# EE318.net
KiCad netlist of a schematic drawn in Altium Designer
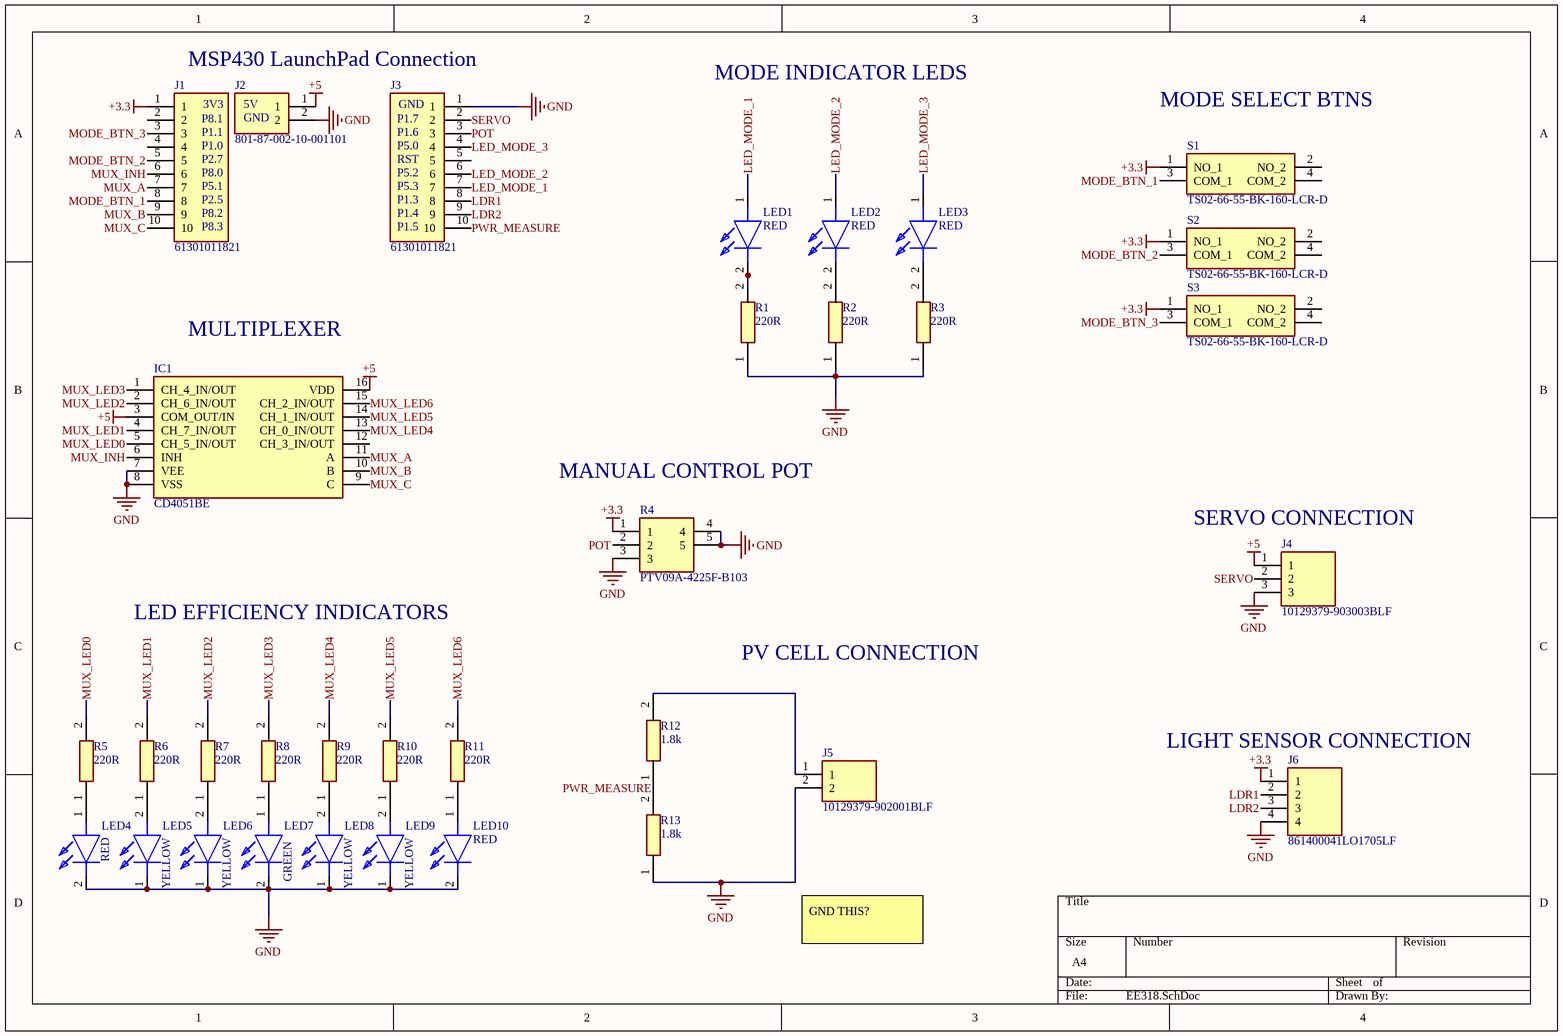
[diagram p0: EE318.SchDoc]

(export (version "E")
  (design (tool "Eeschema 10.0.6"))
  (components
    (comp (ref "IC1")
      (value "CD4051BE")
      (footprint "EE318-PcbLib:DIP794W53P254L1930H508Q16N")
      (description "Multiplexer")
      (fields (field (name "MOUSER PART NUMBER") "595-CD4051BE"))
      (libsource (lib "EE318-Schlib") (part "CD4051BE"))
    )
    (comp (ref "J1")
      (value "61301011821")
      (footprint "EE318-PcbLib:RHDR10W60P0X254_1X10_2590X250X850P")
      (description "Connector")
      (fields (field (name "MOUSER PART NUMBER") "710-61301011821"))
      (libsource (lib "") (part "61301011821_1"))
    )
    (comp (ref "J2")
      (value "801-87-002-10-001101")
      (footprint "EE318-PcbLib:RHDR2W60P0X254_1X2_508X254X700P")
      (description "Connector")
      (fields (field (name "MOUSER PART NUMBER") "437-8018700210001101"))
      (libsource (lib "EE318-Schlib") (part "801-87-002-10-001101"))
    )
    (comp (ref "J3")
      (value "61301011821")
      (footprint "EE318-PcbLib:RHDR10W60P0X254_1X10_2590X250X850P")
      (description "Connector")
      (fields (field (name "MOUSER PART NUMBER") "710-61301011821"))
      (libsource (lib "EE318-Schlib") (part "61301011821"))
    )
    (comp (ref "J4")
      (value "10129379-903003BLF")
      (footprint "EE318-PcbLib:10129379903003BLF")
      (description "Connector")
      (fields (field (name "MOUSER PART NUMBER") "649-1012937990303BLF"))
      (libsource (lib "EE318-Schlib") (part "10129379-903003BLF"))
    )
    (comp (ref "J5")
      (value "10129379-902001BLF")
      (footprint "EE318-PcbLib:HDRRA2W67P0X254_1X2_508X254X241P")
      (description "Connector")
      (fields (field (name "MOUSER PART NUMBER") "649-1012937990201BLF"))
      (libsource (lib "EE318-Schlib") (part "10129379-902001BLF"))
    )
    (comp (ref "J6")
      (value "861400041LO1705LF")
      (footprint "EE318-PcbLib:HDRRA4W63P0X254_1X4_1016X260X264P")
      (description "Connector")
      (fields (field (name "MOUSER PART NUMBER") "649-86140041LO1705LF"))
      (libsource (lib "EE318-Schlib") (part "861400041LO1705LF"))
    )
    (comp (ref "LED1")
      (value "RED")
      (footprint "EE318-PcbLib:C503BRCNCW0Z0AA2")
      (description "LED")
      (fields
        (field (name "MANUFACTURER_PART_NUMBER") "C503B-RCN-CW0Z0AA2")
        (field (name "MOUSER PART NUMBER") "941-C503BRCNCW0Z0AA2")
      )
      (libsource (lib "EE318-Schlib") (part "C503B-RCN-CW0Z0AA2"))
    )
    (comp (ref "LED2")
      (value "RED")
      (footprint "EE318-PcbLib:C503BRCNCW0Z0AA2")
      (description "LED")
      (fields
        (field (name "MANUFACTURER_PART_NUMBER") "C503B-RCN-CW0Z0AA2")
        (field (name "MOUSER PART NUMBER") "941-C503BRCNCW0Z0AA2")
      )
      (libsource (lib "EE318-Schlib") (part "C503B-RCN-CW0Z0AA2"))
    )
    (comp (ref "LED3")
      (value "RED")
      (footprint "EE318-PcbLib:C503BRCNCW0Z0AA2")
      (description "LED")
      (fields
        (field (name "MANUFACTURER_PART_NUMBER") "C503B-RCN-CW0Z0AA2")
        (field (name "MOUSER PART NUMBER") "941-C503BRCNCW0Z0AA2")
      )
      (libsource (lib "EE318-Schlib") (part "C503B-RCN-CW0Z0AA2"))
    )
    (comp (ref "LED4")
      (value "RED")
      (footprint "EE318-PcbLib:C503BRCNCW0Z0AA2")
      (description "LED")
      (fields
        (field (name "MANUFACTURER_PART_NUMBER") "C503B-RCN-CW0Z0AA2")
        (field (name "MOUSER PART NUMBER") "941-C503BRCNCW0Z0AA2")
      )
      (libsource (lib "EE318-Schlib") (part "C503B-RCN-CW0Z0AA2"))
    )
    (comp (ref "LED5")
      (value "YELLOW")
      (footprint "EE318-PcbLib:151051YS04000")
      (description "LED")
      (fields
        (field (name "MANUFACTURER_PART_NUMBER") "151051YS04000")
        (field (name "MOUSER PART NUMBER") "710-151051YS04000")
      )
      (libsource (lib "EE318-Schlib") (part "151051YS04000"))
    )
    (comp (ref "LED6")
      (value "YELLOW")
      (footprint "EE318-PcbLib:151051YS04000")
      (description "LED")
      (fields
        (field (name "MANUFACTURER_PART_NUMBER") "151051YS04000")
        (field (name "MOUSER PART NUMBER") "710-151051YS04000")
      )
      (libsource (lib "EE318-Schlib") (part "151051YS04000"))
    )
    (comp (ref "LED7")
      (value "GREEN")
      (footprint "EE318-PcbLib:C503BGANCB0F0791")
      (description "LED")
      (fields
        (field (name "MANUFACTURER_PART_NUMBER") "C503B-GAN-CB0F0791")
        (field (name "MOUSER PART NUMBER") "941-C503BGANCB0F0791")
      )
      (libsource (lib "EE318-Schlib") (part "C503B-GAN-CB0F0791"))
    )
    (comp (ref "LED8")
      (value "YELLOW")
      (footprint "EE318-PcbLib:151051YS04000")
      (description "LED")
      (fields
        (field (name "MANUFACTURER_PART_NUMBER") "151051YS04000")
        (field (name "MOUSER PART NUMBER") "710-151051YS04000")
      )
      (libsource (lib "EE318-Schlib") (part "151051YS04000"))
    )
    (comp (ref "LED9")
      (value "YELLOW")
      (footprint "EE318-PcbLib:151051YS04000")
      (description "LED")
      (fields
        (field (name "MANUFACTURER_PART_NUMBER") "151051YS04000")
        (field (name "MOUSER PART NUMBER") "710-151051YS04000")
      )
      (libsource (lib "EE318-Schlib") (part "151051YS04000"))
    )
    (comp (ref "LED10")
      (value "RED")
      (footprint "EE318-PcbLib:C503BRCNCW0Z0AA2")
      (description "LED")
      (fields
        (field (name "MANUFACTURER_PART_NUMBER") "C503B-RCN-CW0Z0AA2")
        (field (name "MOUSER PART NUMBER") "941-C503BRCNCW0Z0AA2")
      )
      (libsource (lib "EE318-Schlib") (part "C503B-RCN-CW0Z0AA2"))
    )
    (comp (ref "R1")
      (value "220R")
      (footprint "SamacSys:RESC3116X65N")
      (description "Resistor")
      (fields
        (field (name "MANUFACTURER_PART_NUMBER") "CRS1206QFX-1002ELF")
        (field (name "MOUSER PART NUMBER") "652-CRS1206QFX-1002E")
      )
      (libsource (lib "*") (part "CRS1206QFX-1002ELF"))
    )
    (comp (ref "R2")
      (value "220R")
      (footprint "SamacSys:RESC3116X65N")
      (description "Resistor")
      (fields
        (field (name "MANUFACTURER_PART_NUMBER") "CRS1206QFX-1002ELF")
        (field (name "MOUSER PART NUMBER") "652-CRS1206QFX-1002E")
      )
      (libsource (lib "*") (part "CRS1206QFX-1002ELF"))
    )
    (comp (ref "R3")
      (value "220R")
      (footprint "SamacSys:RESC3116X65N")
      (description "Resistor")
      (fields
        (field (name "MANUFACTURER_PART_NUMBER") "CRS1206QFX-1002ELF")
        (field (name "MOUSER PART NUMBER") "652-CRS1206QFX-1002E")
      )
      (libsource (lib "*") (part "CRS1206QFX-1002ELF"))
    )
    (comp (ref "R4")
      (value "PTV09A-4225F-B103")
      (footprint "EE318-PcbLib:PTV09A4020FB103")
      (description "Potentiometer")
      (fields (field (name "RS PART NUMBER") "8274990P"))
      (libsource (lib "EE318-Schlib") (part "PTV09A-4225F-B103"))
    )
    (comp (ref "R5")
      (value "220R")
      (footprint "SamacSys:RESC3116X65N")
      (description "Resistor")
      (fields
        (field (name "MANUFACTURER_PART_NUMBER") "CRS1206QFX-1002ELF")
        (field (name "MOUSER PART NUMBER") "652-CRS1206QFX-1002E")
      )
      (libsource (lib "*") (part "CRS1206QFX-1002ELF"))
    )
    (comp (ref "R6")
      (value "220R")
      (footprint "SamacSys:RESC3116X65N")
      (description "Resistor")
      (fields
        (field (name "MANUFACTURER_PART_NUMBER") "CRS1206QFX-1002ELF")
        (field (name "MOUSER PART NUMBER") "652-CRS1206QFX-1002E")
      )
      (libsource (lib "*") (part "CRS1206QFX-1002ELF"))
    )
    (comp (ref "R7")
      (value "220R")
      (footprint "SamacSys:RESC3116X65N")
      (description "Resistor")
      (fields
        (field (name "MANUFACTURER_PART_NUMBER") "CRS1206QFX-1002ELF")
        (field (name "MOUSER PART NUMBER") "652-CRS1206QFX-1002E")
      )
      (libsource (lib "*") (part "CRS1206QFX-1002ELF"))
    )
    (comp (ref "R8")
      (value "220R")
      (footprint "SamacSys:RESC3116X65N")
      (description "Resistor")
      (fields
        (field (name "MANUFACTURER_PART_NUMBER") "CRS1206QFX-1002ELF")
        (field (name "MOUSER PART NUMBER") "652-CRS1206QFX-1002E")
      )
      (libsource (lib "*") (part "CRS1206QFX-1002ELF"))
    )
    (comp (ref "R9")
      (value "220R")
      (footprint "SamacSys:RESC3116X65N")
      (description "Resistor")
      (fields
        (field (name "MANUFACTURER_PART_NUMBER") "CRS1206QFX-1002ELF")
        (field (name "MOUSER PART NUMBER") "652-CRS1206QFX-1002E")
      )
      (libsource (lib "*") (part "CRS1206QFX-1002ELF"))
    )
    (comp (ref "R10")
      (value "220R")
      (footprint "SamacSys:RESC3116X65N")
      (description "Resistor")
      (fields
        (field (name "MANUFACTURER_PART_NUMBER") "CRS1206QFX-1002ELF")
        (field (name "MOUSER PART NUMBER") "652-CRS1206QFX-1002E")
      )
      (libsource (lib "*") (part "CRS1206QFX-1002ELF"))
    )
    (comp (ref "R11")
      (value "220R")
      (footprint "SamacSys:RESC3116X65N")
      (description "Resistor")
      (fields
        (field (name "MANUFACTURER_PART_NUMBER") "CRS1206QFX-1002ELF")
        (field (name "MOUSER PART NUMBER") "652-CRS1206QFX-1002E")
      )
      (libsource (lib "*") (part "CRS1206QFX-1002ELF"))
    )
    (comp (ref "R12")
      (value "1.8k")
      (footprint "SamacSys:RESC3116X65N")
      (description "Resistor")
      (fields
        (field (name "MANUFACTURER_PART_NUMBER") "CRS1206QFX-1002ELF")
        (field (name "MOUSER PART NUMBER") "652-CRS1206QFX-1002E")
      )
      (libsource (lib "*") (part "CRS1206QFX-1002ELF"))
    )
    (comp (ref "R13")
      (value "1.8k")
      (footprint "SamacSys:RESC3116X65N")
      (description "Resistor")
      (fields
        (field (name "MANUFACTURER_PART_NUMBER") "CRS1206QFX-1002ELF")
        (field (name "MOUSER PART NUMBER") "652-CRS1206QFX-1002E")
      )
      (libsource (lib "*") (part "CRS1206QFX-1002ELF"))
    )
    (comp (ref "S1")
      (value "TS02-66-55-BK-160-LCR-D")
      (footprint "EE318-PcbLib:TS026655BK160LCRD")
      (description "Switch")
      (fields (field (name "MOUSER PART NUMBER") "179-TS026655BK160LCR"))
      (libsource (lib "EE318-Schlib") (part "TS02-66-55-BK-160-LCR-D"))
    )
    (comp (ref "S2")
      (value "TS02-66-55-BK-160-LCR-D")
      (footprint "EE318-PcbLib:TS026655BK160LCRD")
      (description "Switch")
      (fields (field (name "MOUSER PART NUMBER") "179-TS026655BK160LCR"))
      (libsource (lib "EE318-Schlib") (part "TS02-66-55-BK-160-LCR-D"))
    )
    (comp (ref "S3")
      (value "TS02-66-55-BK-160-LCR-D")
      (footprint "EE318-PcbLib:TS026655BK160LCRD")
      (description "Switch")
      (fields (field (name "MOUSER PART NUMBER") "179-TS026655BK160LCR"))
      (libsource (lib "EE318-Schlib") (part "TS02-66-55-BK-160-LCR-D"))
    )
  )
  (nets
    (net (code "1") (name "+3.3") (class "Default")
      (node (ref "J1") (pin "1") (pinfunction "1_1") (pintype "passive"))
      (node (ref "J6") (pin "1") (pinfunction "1_1") (pintype "passive"))
      (node (ref "R4") (pin "1") (pinfunction "1_1") (pintype "passive"))
      (node (ref "S1") (pin "1") (pinfunction "NO_1_1") (pintype "passive"))
      (node (ref "S2") (pin "1") (pinfunction "NO_1_1") (pintype "passive"))
      (node (ref "S3") (pin "1") (pinfunction "NO_1_1") (pintype "passive"))
    )
    (net (code "2") (name "+5") (class "Default")
      (node (ref "IC1") (pin "16") (pinfunction "VDD_16") (pintype "passive"))
      (node (ref "IC1") (pin "3") (pinfunction "COM_OUT/IN_3") (pintype "passive"))
      (node (ref "J2") (pin "1") (pinfunction "1_1") (pintype "passive"))
      (node (ref "J4") (pin "1") (pinfunction "1_1") (pintype "passive"))
    )
    (net (code "3") (name "/LDR1") (class "Default")
      (node (ref "J3") (pin "8") (pinfunction "8_8") (pintype "passive"))
      (node (ref "J6") (pin "2") (pinfunction "2_2") (pintype "passive"))
    )
    (net (code "4") (name "/LDR2") (class "Default")
      (node (ref "J3") (pin "9") (pinfunction "9_9") (pintype "passive"))
      (node (ref "J6") (pin "3") (pinfunction "3_3") (pintype "passive"))
    )
    (net (code "5") (name "/LED_MODE_1") (class "Default")
      (node (ref "J3") (pin "7") (pinfunction "7_7") (pintype "passive"))
      (node (ref "LED1") (pin "1") (pinfunction "A_1") (pintype "passive"))
    )
    (net (code "6") (name "/LED_MODE_2") (class "Default")
      (node (ref "J3") (pin "6") (pinfunction "6_6") (pintype "passive"))
      (node (ref "LED2") (pin "1") (pinfunction "A_1") (pintype "passive"))
    )
    (net (code "7") (name "/LED_MODE_3") (class "Default")
      (node (ref "J3") (pin "4") (pinfunction "4_4") (pintype "passive"))
      (node (ref "LED3") (pin "1") (pinfunction "A_1") (pintype "passive"))
    )
    (net (code "8") (name "/MODE_BTN_1") (class "Default")
      (node (ref "J1") (pin "8") (pinfunction "8_8") (pintype "passive"))
      (node (ref "S1") (pin "3") (pinfunction "COM_1_3") (pintype "passive"))
    )
    (net (code "9") (name "/MODE_BTN_2") (class "Default")
      (node (ref "J1") (pin "5") (pinfunction "5_5") (pintype "passive"))
      (node (ref "S2") (pin "3") (pinfunction "COM_1_3") (pintype "passive"))
    )
    (net (code "10") (name "/MODE_BTN_3") (class "Default")
      (node (ref "J1") (pin "3") (pinfunction "3_3") (pintype "passive"))
      (node (ref "S3") (pin "3") (pinfunction "COM_1_3") (pintype "passive"))
    )
    (net (code "11") (name "/MUX_A") (class "Default")
      (node (ref "IC1") (pin "11") (pinfunction "A_11") (pintype "passive"))
      (node (ref "J1") (pin "7") (pinfunction "7_7") (pintype "passive"))
    )
    (net (code "12") (name "/MUX_B") (class "Default")
      (node (ref "IC1") (pin "10") (pinfunction "B_10") (pintype "passive"))
      (node (ref "J1") (pin "9") (pinfunction "9_9") (pintype "passive"))
    )
    (net (code "13") (name "/MUX_C") (class "Default")
      (node (ref "IC1") (pin "9") (pinfunction "C_9") (pintype "passive"))
      (node (ref "J1") (pin "10") (pinfunction "10_10") (pintype "passive"))
    )
    (net (code "14") (name "/MUX_INH") (class "Default")
      (node (ref "IC1") (pin "6") (pinfunction "INH_6") (pintype "passive"))
      (node (ref "J1") (pin "6") (pinfunction "6_6") (pintype "passive"))
    )
    (net (code "15") (name "/MUX_LED0") (class "Default")
      (node (ref "IC1") (pin "5") (pinfunction "CH_5_IN/OUT_5") (pintype "passive"))
      (node (ref "R5") (pin "2") (pinfunction "2_2") (pintype "passive"))
    )
    (net (code "16") (name "/MUX_LED1") (class "Default")
      (node (ref "IC1") (pin "4") (pinfunction "CH_7_IN/OUT_4") (pintype "passive"))
      (node (ref "R6") (pin "2") (pinfunction "2_2") (pintype "passive"))
    )
    (net (code "17") (name "/MUX_LED2") (class "Default")
      (node (ref "IC1") (pin "2") (pinfunction "CH_6_IN/OUT_2") (pintype "passive"))
      (node (ref "R7") (pin "2") (pinfunction "2_2") (pintype "passive"))
    )
    (net (code "18") (name "/MUX_LED3") (class "Default")
      (node (ref "IC1") (pin "1") (pinfunction "CH_4_IN/OUT_1") (pintype "passive"))
      (node (ref "R8") (pin "2") (pinfunction "2_2") (pintype "passive"))
    )
    (net (code "19") (name "/MUX_LED4") (class "Default")
      (node (ref "IC1") (pin "13") (pinfunction "CH_0_IN/OUT_13") (pintype "passive"))
      (node (ref "R9") (pin "2") (pinfunction "2_2") (pintype "passive"))
    )
    (net (code "20") (name "/MUX_LED5") (class "Default")
      (node (ref "IC1") (pin "14") (pinfunction "CH_1_IN/OUT_14") (pintype "passive"))
      (node (ref "R10") (pin "2") (pinfunction "2_2") (pintype "passive"))
    )
    (net (code "21") (name "/MUX_LED6") (class "Default")
      (node (ref "IC1") (pin "15") (pinfunction "CH_2_IN/OUT_15") (pintype "passive"))
      (node (ref "R11") (pin "2") (pinfunction "2_2") (pintype "passive"))
    )
    (net (code "22") (name "/POT") (class "Default")
      (node (ref "J3") (pin "3") (pinfunction "3_3") (pintype "passive"))
      (node (ref "R4") (pin "2") (pinfunction "2_2") (pintype "passive"))
    )
    (net (code "23") (name "/PWR_MEASURE") (class "Default")
      (node (ref "J3") (pin "10") (pinfunction "10_10") (pintype "passive"))
      (node (ref "R12") (pin "1") (pinfunction "1_1") (pintype "passive"))
      (node (ref "R13") (pin "2") (pinfunction "2_2") (pintype "passive"))
    )
    (net (code "24") (name "/SERVO") (class "Default")
      (node (ref "J3") (pin "2") (pinfunction "2_2") (pintype "passive"))
      (node (ref "J4") (pin "2") (pinfunction "2_2") (pintype "passive"))
    )
    (net (code "25") (name "GND") (class "Default")
      (node (ref "IC1") (pin "7") (pinfunction "VEE_7") (pintype "passive"))
      (node (ref "IC1") (pin "8") (pinfunction "VSS_8") (pintype "passive"))
      (node (ref "J2") (pin "2") (pinfunction "2_2") (pintype "passive"))
      (node (ref "J3") (pin "1") (pinfunction "1_1") (pintype "passive"))
      (node (ref "J4") (pin "3") (pinfunction "3_3") (pintype "passive"))
      (node (ref "J5") (pin "2") (pinfunction "2_2") (pintype "passive"))
      (node (ref "J6") (pin "4") (pinfunction "4_4") (pintype "passive"))
      (node (ref "LED10") (pin "2") (pinfunction "K_2") (pintype "passive"))
      (node (ref "LED4") (pin "2") (pinfunction "K_2") (pintype "passive"))
      (node (ref "LED5") (pin "1") (pinfunction "K_1") (pintype "passive"))
      (node (ref "LED6") (pin "1") (pinfunction "K_1") (pintype "passive"))
      (node (ref "LED7") (pin "2") (pinfunction "K_2") (pintype "passive"))
      (node (ref "LED8") (pin "1") (pinfunction "K_1") (pintype "passive"))
      (node (ref "LED9") (pin "1") (pinfunction "K_1") (pintype "passive"))
      (node (ref "R1") (pin "1") (pinfunction "1_1") (pintype "passive"))
      (node (ref "R13") (pin "1") (pinfunction "1_1") (pintype "passive"))
      (node (ref "R2") (pin "1") (pinfunction "1_1") (pintype "passive"))
      (node (ref "R3") (pin "1") (pinfunction "1_1") (pintype "passive"))
      (node (ref "R4") (pin "3") (pinfunction "3_3") (pintype "passive"))
      (node (ref "R4") (pin "4") (pinfunction "4_4") (pintype "passive"))
      (node (ref "R4") (pin "5") (pinfunction "5_5") (pintype "passive"))
    )
    (net (code "26") (name "Net-(J5-Pad1)") (class "Default")
      (node (ref "J5") (pin "1") (pinfunction "1_1") (pintype "passive"))
      (node (ref "R12") (pin "2") (pinfunction "2_2") (pintype "passive"))
    )
    (net (code "27") (name "Net-(LED1-K)") (class "Default")
      (node (ref "LED1") (pin "2") (pinfunction "K_2") (pintype "passive"))
      (node (ref "R1") (pin "2") (pinfunction "2_2") (pintype "passive"))
    )
    (net (code "28") (name "Net-(LED2-K)") (class "Default")
      (node (ref "LED2") (pin "2") (pinfunction "K_2") (pintype "passive"))
      (node (ref "R2") (pin "2") (pinfunction "2_2") (pintype "passive"))
    )
    (net (code "29") (name "Net-(LED3-K)") (class "Default")
      (node (ref "LED3") (pin "2") (pinfunction "K_2") (pintype "passive"))
      (node (ref "R3") (pin "2") (pinfunction "2_2") (pintype "passive"))
    )
    (net (code "30") (name "Net-(LED4-A)") (class "Default")
      (node (ref "LED4") (pin "1") (pinfunction "A_1") (pintype "passive"))
      (node (ref "R5") (pin "1") (pinfunction "1_1") (pintype "passive"))
    )
    (net (code "31") (name "Net-(LED5-A)") (class "Default")
      (node (ref "LED5") (pin "2") (pinfunction "A_2") (pintype "passive"))
      (node (ref "R6") (pin "1") (pinfunction "1_1") (pintype "passive"))
    )
    (net (code "32") (name "Net-(LED6-A)") (class "Default")
      (node (ref "LED6") (pin "2") (pinfunction "A_2") (pintype "passive"))
      (node (ref "R7") (pin "1") (pinfunction "1_1") (pintype "passive"))
    )
    (net (code "33") (name "Net-(LED7-A)") (class "Default")
      (node (ref "LED7") (pin "1") (pinfunction "A_1") (pintype "passive"))
      (node (ref "R8") (pin "1") (pinfunction "1_1") (pintype "passive"))
    )
    (net (code "34") (name "Net-(LED8-A)") (class "Default")
      (node (ref "LED8") (pin "2") (pinfunction "A_2") (pintype "passive"))
      (node (ref "R9") (pin "1") (pinfunction "1_1") (pintype "passive"))
    )
    (net (code "35") (name "Net-(LED9-A)") (class "Default")
      (node (ref "LED9") (pin "2") (pinfunction "A_2") (pintype "passive"))
      (node (ref "R10") (pin "1") (pinfunction "1_1") (pintype "passive"))
    )
    (net (code "36") (name "Net-(LED10-A)") (class "Default")
      (node (ref "LED10") (pin "1") (pinfunction "A_1") (pintype "passive"))
      (node (ref "R11") (pin "1") (pinfunction "1_1") (pintype "passive"))
    )
    (net (code "37") (name "unconnected-(IC1-CH_3_IN{slash}OUT-Pad12)") (class "Default")
      (node (ref "IC1") (pin "12") (pinfunction "CH_3_IN/OUT_12") (pintype "passive"))
    )
    (net (code "38") (name "unconnected-(J1-Pad2)") (class "Default")
      (node (ref "J1") (pin "2") (pinfunction "2_2") (pintype "passive"))
    )
    (net (code "39") (name "unconnected-(J1-Pad4)") (class "Default")
      (node (ref "J1") (pin "4") (pinfunction "4_4") (pintype "passive"))
    )
    (net (code "40") (name "unconnected-(J3-Pad5)") (class "Default")
      (node (ref "J3") (pin "5") (pinfunction "5_5") (pintype "passive"))
    )
    (net (code "41") (name "unconnected-(S1-COM_2-Pad4)") (class "Default")
      (node (ref "S1") (pin "4") (pinfunction "COM_2_4") (pintype "passive"))
    )
    (net (code "42") (name "unconnected-(S1-NO_2-Pad2)") (class "Default")
      (node (ref "S1") (pin "2") (pinfunction "NO_2_2") (pintype "passive"))
    )
    (net (code "43") (name "unconnected-(S2-COM_2-Pad4)") (class "Default")
      (node (ref "S2") (pin "4") (pinfunction "COM_2_4") (pintype "passive"))
    )
    (net (code "44") (name "unconnected-(S2-NO_2-Pad2)") (class "Default")
      (node (ref "S2") (pin "2") (pinfunction "NO_2_2") (pintype "passive"))
    )
    (net (code "45") (name "unconnected-(S3-COM_2-Pad4)") (class "Default")
      (node (ref "S3") (pin "4") (pinfunction "COM_2_4") (pintype "passive"))
    )
    (net (code "46") (name "unconnected-(S3-NO_2-Pad2)") (class "Default")
      (node (ref "S3") (pin "2") (pinfunction "NO_2_2") (pintype "passive"))
    )
  )
)
